# DAC.net
KiCad netlist of a schematic drawn in Altium Designer
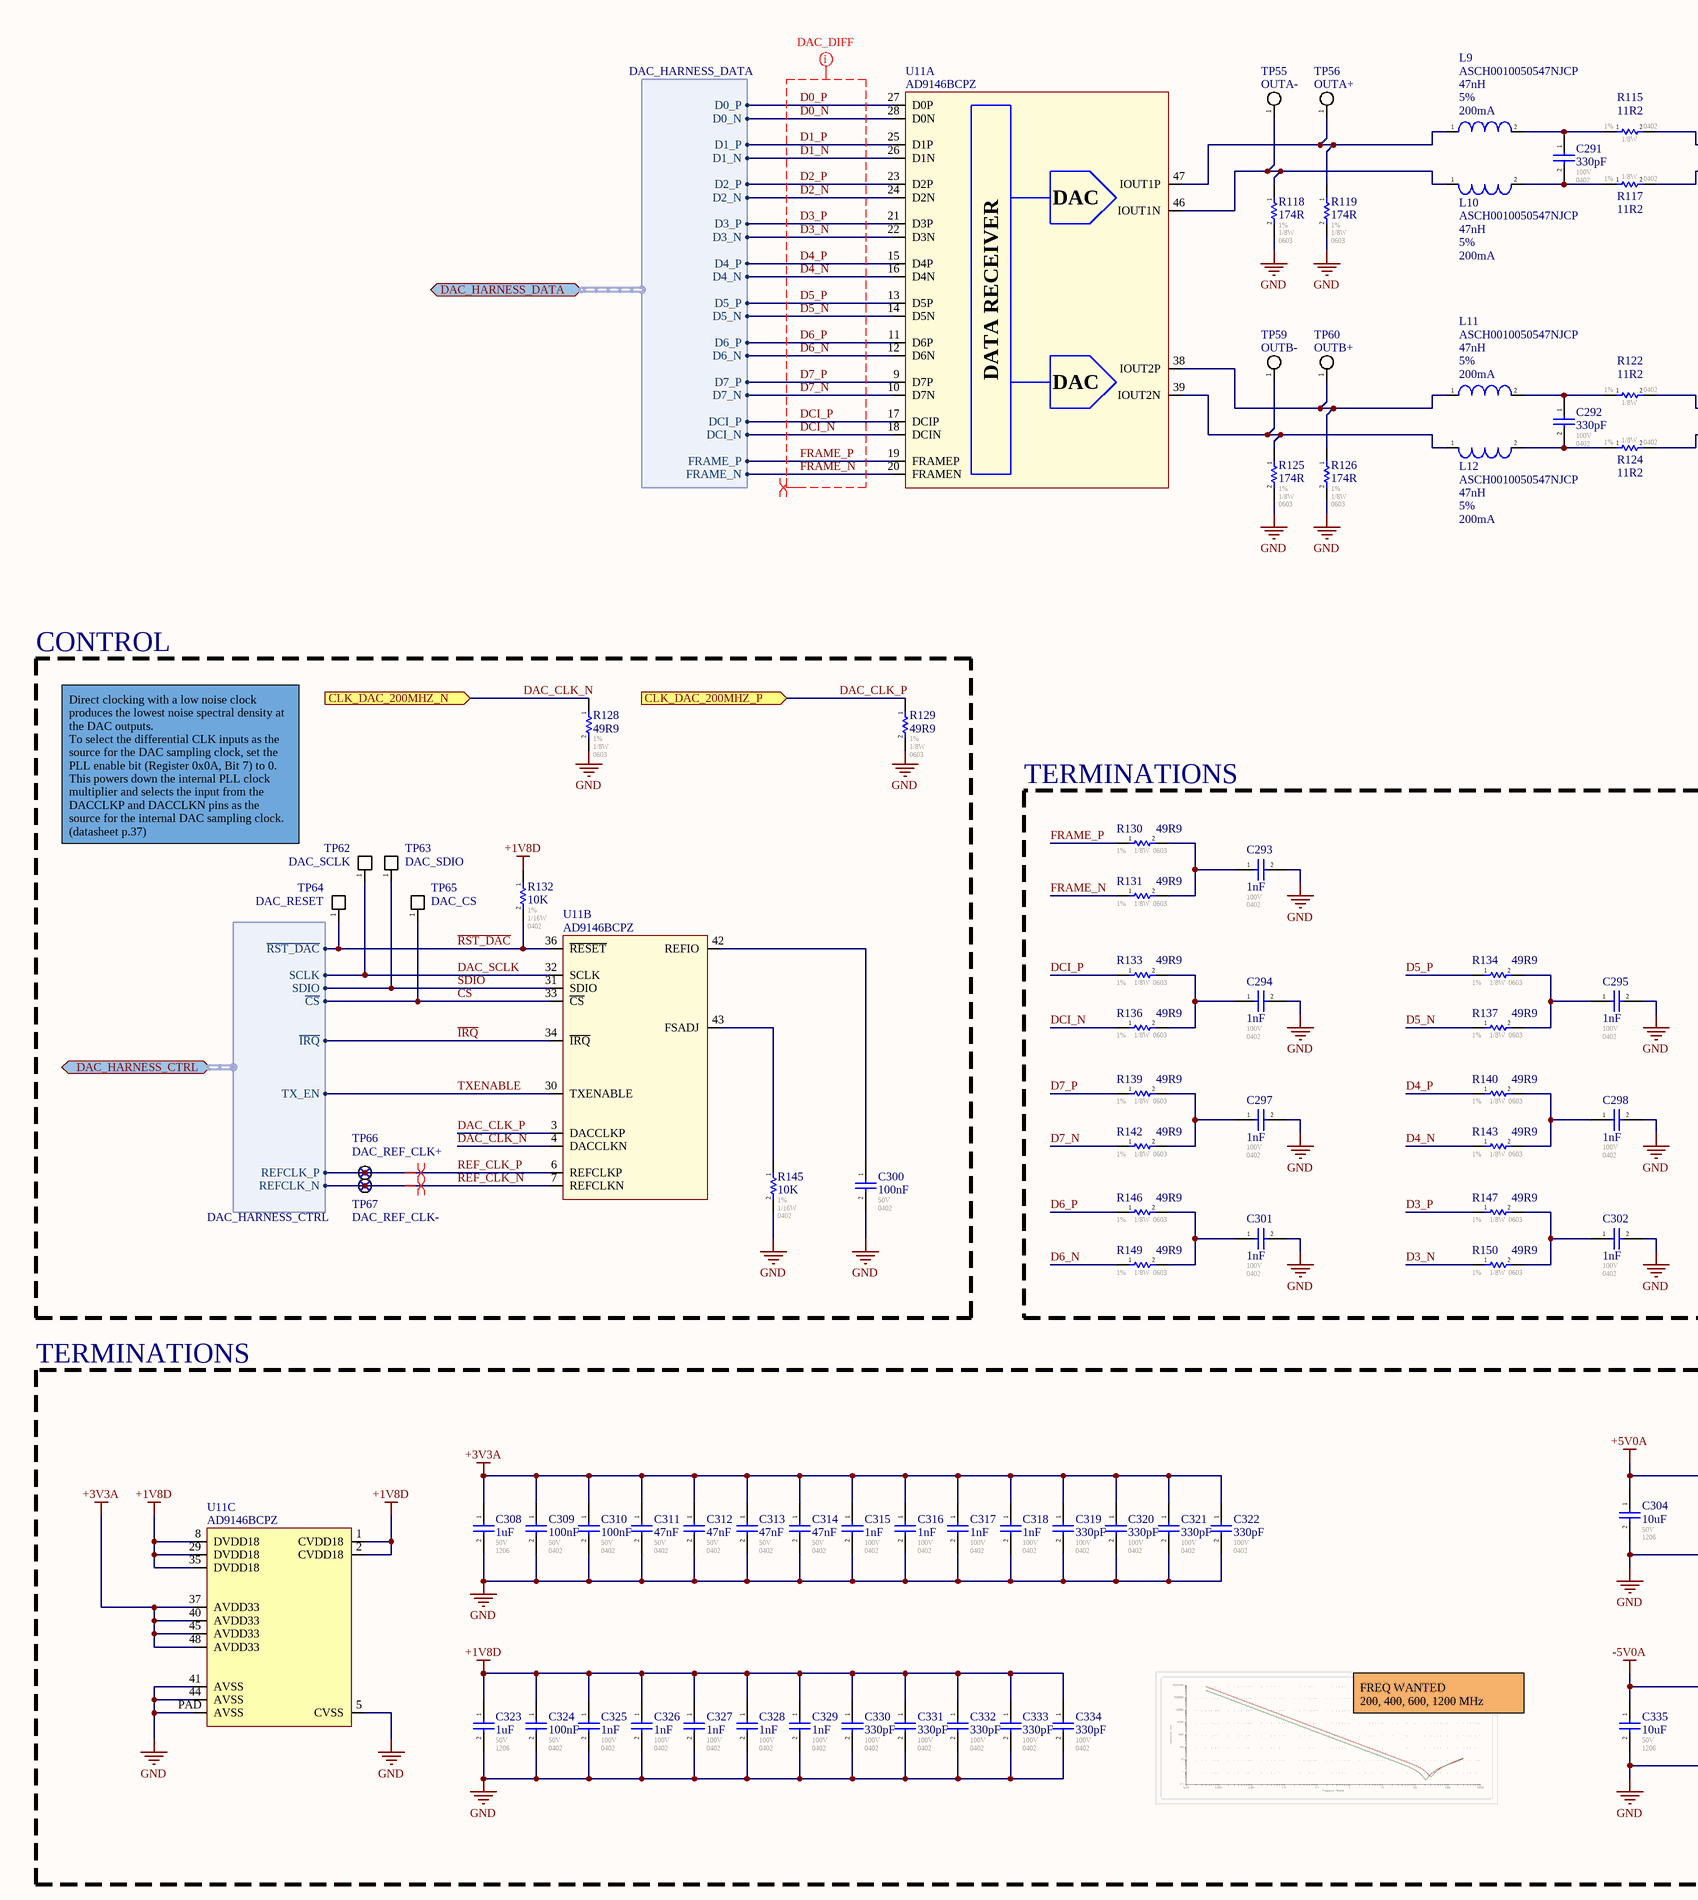
[diagram p0: DAC.SchDoc, left]
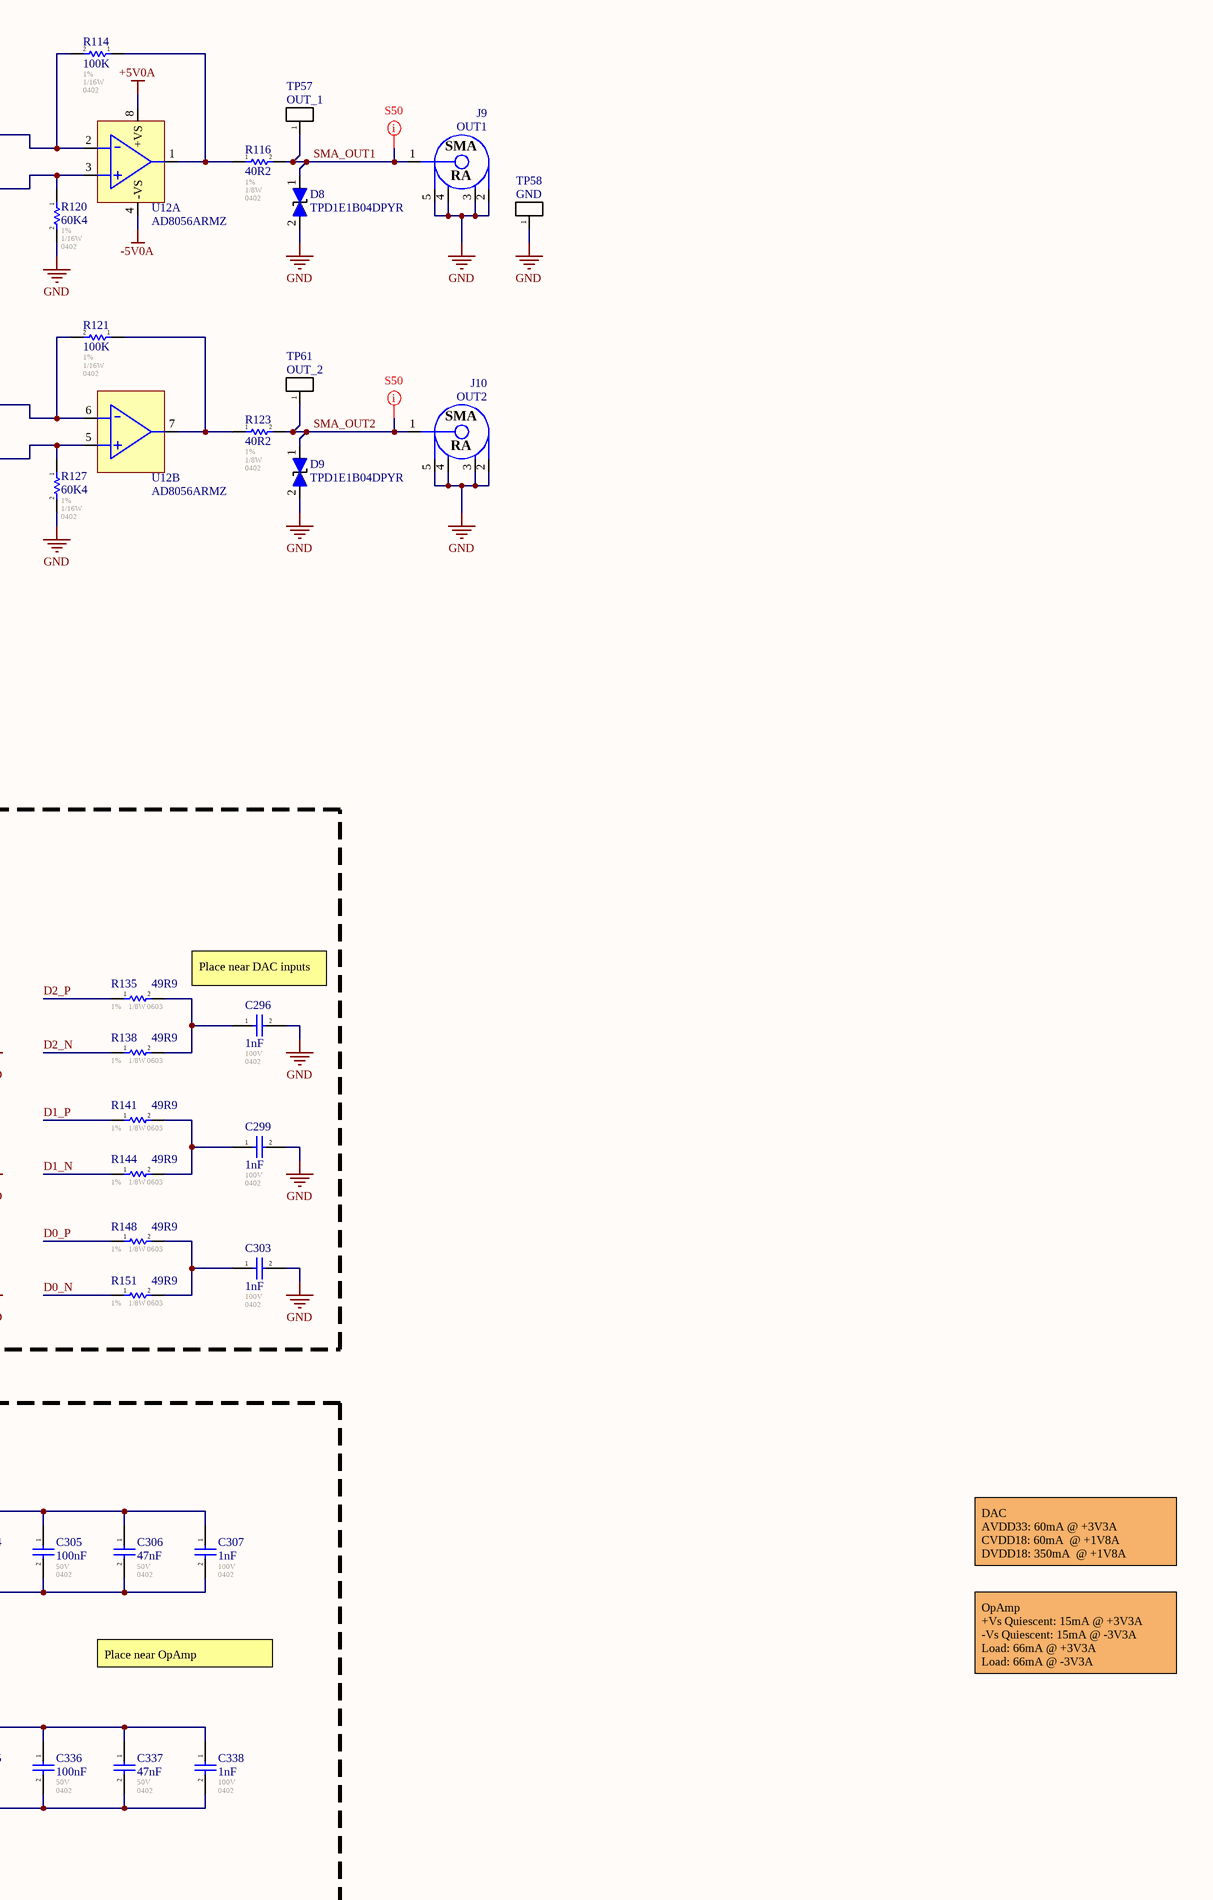
[diagram p1: DAC.SchDoc, right]

(export (version "E")
  (design (tool "Eeschema 10.0.6"))
  (components
    (comp (ref "C291")
      (value "330pF")
      (footprint "0402")
      (description "GCM155R72A331KA37D\r\n0402 330pF 10% X7R Ceramic Capacitor")
      (fields
        (field (name "MFR") "Murata")
        (field (name "PART#") "GCM155R72A331KA37D")
        (field (name "VOLTAGE - RATED") "100V")
      )
      (libsource (lib "Symbols") (part "CAP_CER"))
    )
    (comp (ref "C292")
      (value "330pF")
      (footprint "0402")
      (description "GCM155R72A331KA37D\r\n0402 330pF 10% X7R Ceramic Capacitor")
      (fields
        (field (name "MFR") "Murata")
        (field (name "PART#") "GCM155R72A331KA37D")
        (field (name "VOLTAGE - RATED") "100V")
      )
      (libsource (lib "Symbols") (part "CAP_CER"))
    )
    (comp (ref "C293")
      (value "1nF")
      (footprint "0402")
      (description "GCM155R72A102KA37D\r\n0402 1nF 10% X7R Ceramic Capacitor")
      (fields
        (field (name "MFR") "Murata")
        (field (name "PART#") "GCM155R72A102KA37D")
        (field (name "VOLTAGE - RATED") "100V")
      )
      (libsource (lib "Symbols") (part "CAP_CER"))
    )
    (comp (ref "C294")
      (value "1nF")
      (footprint "0402")
      (description "GCM155R72A102KA37D\r\n0402 1nF 10% X7R Ceramic Capacitor")
      (fields
        (field (name "MFR") "Murata")
        (field (name "PART#") "GCM155R72A102KA37D")
        (field (name "VOLTAGE - RATED") "100V")
      )
      (libsource (lib "Symbols") (part "CAP_CER"))
    )
    (comp (ref "C295")
      (value "1nF")
      (footprint "0402")
      (description "GCM155R72A102KA37D\r\n0402 1nF 10% X7R Ceramic Capacitor")
      (fields
        (field (name "MFR") "Murata")
        (field (name "PART#") "GCM155R72A102KA37D")
        (field (name "VOLTAGE - RATED") "100V")
      )
      (libsource (lib "Symbols") (part "CAP_CER"))
    )
    (comp (ref "C296")
      (value "1nF")
      (footprint "0402")
      (description "GCM155R72A102KA37D\r\n0402 1nF 10% X7R Ceramic Capacitor")
      (fields
        (field (name "MFR") "Murata")
        (field (name "PART#") "GCM155R72A102KA37D")
        (field (name "VOLTAGE - RATED") "100V")
      )
      (libsource (lib "Symbols") (part "CAP_CER"))
    )
    (comp (ref "C297")
      (value "1nF")
      (footprint "0402")
      (description "GCM155R72A102KA37D\r\n0402 1nF 10% X7R Ceramic Capacitor")
      (fields
        (field (name "MFR") "Murata")
        (field (name "PART#") "GCM155R72A102KA37D")
        (field (name "VOLTAGE - RATED") "100V")
      )
      (libsource (lib "Symbols") (part "CAP_CER"))
    )
    (comp (ref "C298")
      (value "1nF")
      (footprint "0402")
      (description "GCM155R72A102KA37D\r\n0402 1nF 10% X7R Ceramic Capacitor")
      (fields
        (field (name "MFR") "Murata")
        (field (name "PART#") "GCM155R72A102KA37D")
        (field (name "VOLTAGE - RATED") "100V")
      )
      (libsource (lib "Symbols") (part "CAP_CER"))
    )
    (comp (ref "C299")
      (value "1nF")
      (footprint "0402")
      (description "GCM155R72A102KA37D\r\n0402 1nF 10% X7R Ceramic Capacitor")
      (fields
        (field (name "MFR") "Murata")
        (field (name "PART#") "GCM155R72A102KA37D")
        (field (name "VOLTAGE - RATED") "100V")
      )
      (libsource (lib "Symbols") (part "CAP_CER"))
    )
    (comp (ref "C300")
      (value "100nF")
      (footprint "0402")
      (description "GCM155R71H104KE02J\r\n0402 100nF 10% X7R Ceramic Capacitor")
      (fields
        (field (name "MFR") "Murata")
        (field (name "PART#") "GCM155R71H104KE02J")
        (field (name "VOLTAGE - RATED") "50V")
      )
      (libsource (lib "Symbols") (part "CAP_CER"))
    )
    (comp (ref "C301")
      (value "1nF")
      (footprint "0402")
      (description "GCM155R72A102KA37D\r\n0402 1nF 10% X7R Ceramic Capacitor")
      (fields
        (field (name "MFR") "Murata")
        (field (name "PART#") "GCM155R72A102KA37D")
        (field (name "VOLTAGE - RATED") "100V")
      )
      (libsource (lib "Symbols") (part "CAP_CER"))
    )
    (comp (ref "C302")
      (value "1nF")
      (footprint "0402")
      (description "GCM155R72A102KA37D\r\n0402 1nF 10% X7R Ceramic Capacitor")
      (fields
        (field (name "MFR") "Murata")
        (field (name "PART#") "GCM155R72A102KA37D")
        (field (name "VOLTAGE - RATED") "100V")
      )
      (libsource (lib "Symbols") (part "CAP_CER"))
    )
    (comp (ref "C303")
      (value "1nF")
      (footprint "0402")
      (description "GCM155R72A102KA37D\r\n0402 1nF 10% X7R Ceramic Capacitor")
      (fields
        (field (name "MFR") "Murata")
        (field (name "PART#") "GCM155R72A102KA37D")
        (field (name "VOLTAGE - RATED") "100V")
      )
      (libsource (lib "Symbols") (part "CAP_CER"))
    )
    (comp (ref "C304")
      (value "10uF")
      (footprint "1206")
      (description "GRT31CR61H106KE01L\r\n1206 10uF 10% X5R Ceramic Capacitor")
      (fields
        (field (name "MFR") "Murata")
        (field (name "VOLTAGE - RATED") "50V")
        (field (name "TOLERANCE") "10%")
      )
      (libsource (lib "Symbols") (part "CAP_CER"))
    )
    (comp (ref "C305")
      (value "100nF")
      (footprint "0402")
      (description "GCM155R71H104KE02J\r\n0402 100nF 10% X7R Ceramic Capacitor")
      (fields
        (field (name "MFR") "Murata")
        (field (name "PART#") "GCM155R71H104KE02J")
        (field (name "VOLTAGE - RATED") "50V")
      )
      (libsource (lib "Symbols") (part "CAP_CER"))
    )
    (comp (ref "C306")
      (value "47nF")
      (footprint "0402")
      (description "GCM155R71H473KE02J\r\n0402 47nF 10% X7R Ceramic Capacitor")
      (fields
        (field (name "MFR") "Murata")
        (field (name "PART#") "GCM155R71H473KE02J")
        (field (name "VOLTAGE - RATED") "50V")
      )
      (libsource (lib "Symbols") (part "CAP_CER"))
    )
    (comp (ref "C307")
      (value "1nF")
      (footprint "0402")
      (description "GCM155R72A102KA37D\r\n0402 1nF 10% X7R Ceramic Capacitor")
      (fields
        (field (name "MFR") "Murata")
        (field (name "PART#") "GCM155R72A102KA37D")
        (field (name "VOLTAGE - RATED") "100V")
      )
      (libsource (lib "Symbols") (part "CAP_CER"))
    )
    (comp (ref "C308")
      (value "1uF")
      (footprint "1206")
      (description "GCJ31CR71H105KA12L\r\n1206 1uF 10% X7R Ceramic Capacitor")
      (fields
        (field (name "MFR") "Murata")
        (field (name "PART#") "GCJ31CR71H105KA12L")
        (field (name "VOLTAGE - RATED") "50V")
      )
      (libsource (lib "Symbols") (part "CAP_CER"))
    )
    (comp (ref "C309")
      (value "100nF")
      (footprint "0402")
      (description "GCM155R71H104KE02J\r\n0402 100nF 10% X7R Ceramic Capacitor")
      (fields
        (field (name "MFR") "Murata")
        (field (name "PART#") "GCM155R71H104KE02J")
        (field (name "VOLTAGE - RATED") "50V")
      )
      (libsource (lib "Symbols") (part "CAP_CER"))
    )
    (comp (ref "C310")
      (value "100nF")
      (footprint "0402")
      (description "GCM155R71H104KE02J\r\n0402 100nF 10% X7R Ceramic Capacitor")
      (fields
        (field (name "MFR") "Murata")
        (field (name "PART#") "GCM155R71H104KE02J")
        (field (name "VOLTAGE - RATED") "50V")
      )
      (libsource (lib "Symbols") (part "CAP_CER"))
    )
    (comp (ref "C311")
      (value "47nF")
      (footprint "0402")
      (description "GCM155R71H473KE02J\r\n0402 47nF 10% X7R Ceramic Capacitor")
      (fields
        (field (name "MFR") "Murata")
        (field (name "PART#") "GCM155R71H473KE02J")
        (field (name "VOLTAGE - RATED") "50V")
      )
      (libsource (lib "Symbols") (part "CAP_CER"))
    )
    (comp (ref "C312")
      (value "47nF")
      (footprint "0402")
      (description "GCM155R71H473KE02J\r\n0402 47nF 10% X7R Ceramic Capacitor")
      (fields
        (field (name "MFR") "Murata")
        (field (name "PART#") "GCM155R71H473KE02J")
        (field (name "VOLTAGE - RATED") "50V")
      )
      (libsource (lib "Symbols") (part "CAP_CER"))
    )
    (comp (ref "C313")
      (value "47nF")
      (footprint "0402")
      (description "GCM155R71H473KE02J\r\n0402 47nF 10% X7R Ceramic Capacitor")
      (fields
        (field (name "MFR") "Murata")
        (field (name "PART#") "GCM155R71H473KE02J")
        (field (name "VOLTAGE - RATED") "50V")
      )
      (libsource (lib "Symbols") (part "CAP_CER"))
    )
    (comp (ref "C314")
      (value "47nF")
      (footprint "0402")
      (description "GCM155R71H473KE02J\r\n0402 47nF 10% X7R Ceramic Capacitor")
      (fields
        (field (name "MFR") "Murata")
        (field (name "PART#") "GCM155R71H473KE02J")
        (field (name "VOLTAGE - RATED") "50V")
      )
      (libsource (lib "Symbols") (part "CAP_CER"))
    )
    (comp (ref "C315")
      (value "1nF")
      (footprint "0402")
      (description "GCM155R72A102KA37D\r\n0402 1nF 10% X7R Ceramic Capacitor")
      (fields
        (field (name "MFR") "Murata")
        (field (name "PART#") "GCM155R72A102KA37D")
        (field (name "VOLTAGE - RATED") "100V")
      )
      (libsource (lib "Symbols") (part "CAP_CER"))
    )
    (comp (ref "C316")
      (value "1nF")
      (footprint "0402")
      (description "GCM155R72A102KA37D\r\n0402 1nF 10% X7R Ceramic Capacitor")
      (fields
        (field (name "MFR") "Murata")
        (field (name "PART#") "GCM155R72A102KA37D")
        (field (name "VOLTAGE - RATED") "100V")
      )
      (libsource (lib "Symbols") (part "CAP_CER"))
    )
    (comp (ref "C317")
      (value "1nF")
      (footprint "0402")
      (description "GCM155R72A102KA37D\r\n0402 1nF 10% X7R Ceramic Capacitor")
      (fields
        (field (name "MFR") "Murata")
        (field (name "PART#") "GCM155R72A102KA37D")
        (field (name "VOLTAGE - RATED") "100V")
      )
      (libsource (lib "Symbols") (part "CAP_CER"))
    )
    (comp (ref "C318")
      (value "1nF")
      (footprint "0402")
      (description "GCM155R72A102KA37D\r\n0402 1nF 10% X7R Ceramic Capacitor")
      (fields
        (field (name "MFR") "Murata")
        (field (name "PART#") "GCM155R72A102KA37D")
        (field (name "VOLTAGE - RATED") "100V")
      )
      (libsource (lib "Symbols") (part "CAP_CER"))
    )
    (comp (ref "C319")
      (value "330pF")
      (footprint "0402")
      (description "GCM155R72A331KA37D\r\n0402 330pF 10% X7R Ceramic Capacitor")
      (fields
        (field (name "MFR") "Murata")
        (field (name "PART#") "GCM155R72A331KA37D")
        (field (name "VOLTAGE - RATED") "100V")
      )
      (libsource (lib "Symbols") (part "CAP_CER"))
    )
    (comp (ref "C320")
      (value "330pF")
      (footprint "0402")
      (description "GCM155R72A331KA37D\r\n0402 330pF 10% X7R Ceramic Capacitor")
      (fields
        (field (name "MFR") "Murata")
        (field (name "PART#") "GCM155R72A331KA37D")
        (field (name "VOLTAGE - RATED") "100V")
      )
      (libsource (lib "Symbols") (part "CAP_CER"))
    )
    (comp (ref "C321")
      (value "330pF")
      (footprint "0402")
      (description "GCM155R72A331KA37D\r\n0402 330pF 10% X7R Ceramic Capacitor")
      (fields
        (field (name "MFR") "Murata")
        (field (name "PART#") "GCM155R72A331KA37D")
        (field (name "VOLTAGE - RATED") "100V")
      )
      (libsource (lib "Symbols") (part "CAP_CER"))
    )
    (comp (ref "C322")
      (value "330pF")
      (footprint "0402")
      (description "GCM155R72A331KA37D\r\n0402 330pF 10% X7R Ceramic Capacitor")
      (fields
        (field (name "MFR") "Murata")
        (field (name "PART#") "GCM155R72A331KA37D")
        (field (name "VOLTAGE - RATED") "100V")
      )
      (libsource (lib "Symbols") (part "CAP_CER"))
    )
    (comp (ref "C323")
      (value "1uF")
      (footprint "1206")
      (description "GCJ31CR71H105KA12L\r\n1206 1uF 10% X7R Ceramic Capacitor")
      (fields
        (field (name "MFR") "Murata")
        (field (name "PART#") "GCJ31CR71H105KA12L")
        (field (name "VOLTAGE - RATED") "50V")
      )
      (libsource (lib "Symbols") (part "CAP_CER"))
    )
    (comp (ref "C324")
      (value "100nF")
      (footprint "0402")
      (description "GCM155R71H104KE02J\r\n0402 100nF 10% X7R Ceramic Capacitor")
      (fields
        (field (name "MFR") "Murata")
        (field (name "PART#") "GCM155R71H104KE02J")
        (field (name "VOLTAGE - RATED") "50V")
      )
      (libsource (lib "Symbols") (part "CAP_CER"))
    )
    (comp (ref "C325")
      (value "1nF")
      (footprint "0402")
      (description "GCM155R72A102KA37D\r\n0402 1nF 10% X7R Ceramic Capacitor")
      (fields
        (field (name "MFR") "Murata")
        (field (name "PART#") "GCM155R72A102KA37D")
        (field (name "VOLTAGE - RATED") "100V")
      )
      (libsource (lib "Symbols") (part "CAP_CER"))
    )
    (comp (ref "C326")
      (value "1nF")
      (footprint "0402")
      (description "GCM155R72A102KA37D\r\n0402 1nF 10% X7R Ceramic Capacitor")
      (fields
        (field (name "MFR") "Murata")
        (field (name "PART#") "GCM155R72A102KA37D")
        (field (name "VOLTAGE - RATED") "100V")
      )
      (libsource (lib "Symbols") (part "CAP_CER"))
    )
    (comp (ref "C327")
      (value "1nF")
      (footprint "0402")
      (description "GCM155R72A102KA37D\r\n0402 1nF 10% X7R Ceramic Capacitor")
      (fields
        (field (name "MFR") "Murata")
        (field (name "PART#") "GCM155R72A102KA37D")
        (field (name "VOLTAGE - RATED") "100V")
      )
      (libsource (lib "Symbols") (part "CAP_CER"))
    )
    (comp (ref "C328")
      (value "1nF")
      (footprint "0402")
      (description "GCM155R72A102KA37D\r\n0402 1nF 10% X7R Ceramic Capacitor")
      (fields
        (field (name "MFR") "Murata")
        (field (name "PART#") "GCM155R72A102KA37D")
        (field (name "VOLTAGE - RATED") "100V")
      )
      (libsource (lib "Symbols") (part "CAP_CER"))
    )
    (comp (ref "C329")
      (value "1nF")
      (footprint "0402")
      (description "GCM155R72A102KA37D\r\n0402 1nF 10% X7R Ceramic Capacitor")
      (fields
        (field (name "MFR") "Murata")
        (field (name "PART#") "GCM155R72A102KA37D")
        (field (name "VOLTAGE - RATED") "100V")
      )
      (libsource (lib "Symbols") (part "CAP_CER"))
    )
    (comp (ref "C330")
      (value "330pF")
      (footprint "0402")
      (description "GCM155R72A331KA37D\r\n0402 330pF 10% X7R Ceramic Capacitor")
      (fields
        (field (name "MFR") "Murata")
        (field (name "PART#") "GCM155R72A331KA37D")
        (field (name "VOLTAGE - RATED") "100V")
      )
      (libsource (lib "Symbols") (part "CAP_CER"))
    )
    (comp (ref "C331")
      (value "330pF")
      (footprint "0402")
      (description "GCM155R72A331KA37D\r\n0402 330pF 10% X7R Ceramic Capacitor")
      (fields
        (field (name "MFR") "Murata")
        (field (name "PART#") "GCM155R72A331KA37D")
        (field (name "VOLTAGE - RATED") "100V")
      )
      (libsource (lib "Symbols") (part "CAP_CER"))
    )
    (comp (ref "C332")
      (value "330pF")
      (footprint "0402")
      (description "GCM155R72A331KA37D\r\n0402 330pF 10% X7R Ceramic Capacitor")
      (fields
        (field (name "MFR") "Murata")
        (field (name "PART#") "GCM155R72A331KA37D")
        (field (name "VOLTAGE - RATED") "100V")
      )
      (libsource (lib "Symbols") (part "CAP_CER"))
    )
    (comp (ref "C333")
      (value "330pF")
      (footprint "0402")
      (description "GCM155R72A331KA37D\r\n0402 330pF 10% X7R Ceramic Capacitor")
      (fields
        (field (name "MFR") "Murata")
        (field (name "PART#") "GCM155R72A331KA37D")
        (field (name "VOLTAGE - RATED") "100V")
      )
      (libsource (lib "Symbols") (part "CAP_CER"))
    )
    (comp (ref "C334")
      (value "330pF")
      (footprint "0402")
      (description "GCM155R72A331KA37D\r\n0402 330pF 10% X7R Ceramic Capacitor")
      (fields
        (field (name "MFR") "Murata")
        (field (name "PART#") "GCM155R72A331KA37D")
        (field (name "VOLTAGE - RATED") "100V")
      )
      (libsource (lib "Symbols") (part "CAP_CER"))
    )
    (comp (ref "C335")
      (value "10uF")
      (footprint "1206")
      (description "GRT31CR61H106KE01L\r\n1206 10uF 10% X5R Ceramic Capacitor")
      (fields
        (field (name "MFR") "Murata")
        (field (name "VOLTAGE - RATED") "50V")
        (field (name "TOLERANCE") "10%")
      )
      (libsource (lib "Symbols") (part "CAP_CER"))
    )
    (comp (ref "C336")
      (value "100nF")
      (footprint "0402")
      (description "GCM155R71H104KE02J\r\n0402 100nF 10% X7R Ceramic Capacitor")
      (fields
        (field (name "MFR") "Murata")
        (field (name "PART#") "GCM155R71H104KE02J")
        (field (name "VOLTAGE - RATED") "50V")
      )
      (libsource (lib "Symbols") (part "CAP_CER"))
    )
    (comp (ref "C337")
      (value "47nF")
      (footprint "0402")
      (description "GCM155R71H473KE02J\r\n0402 47nF 10% X7R Ceramic Capacitor")
      (fields
        (field (name "MFR") "Murata")
        (field (name "PART#") "GCM155R71H473KE02J")
        (field (name "VOLTAGE - RATED") "50V")
      )
      (libsource (lib "Symbols") (part "CAP_CER"))
    )
    (comp (ref "C338")
      (value "1nF")
      (footprint "0402")
      (description "GCM155R72A102KA37D\r\n0402 1nF 10% X7R Ceramic Capacitor")
      (fields
        (field (name "MFR") "Murata")
        (field (name "PART#") "GCM155R72A102KA37D")
        (field (name "VOLTAGE - RATED") "100V")
      )
      (libsource (lib "Symbols") (part "CAP_CER"))
    )
    (comp (ref "D8")
      (value "TPD1E1B04DPYR")
      (footprint "TVS_DATA_TPD1E1B04DPYR")
      (description "TVS - TVS DIODE 3.6V 8.5V - 0402")
      (fields
        (field (name "CREATEDBY/DATE") "Keven Deslandes - 2018/10/19")
        (field (name "VERIFIEDBY") "Caroline Paulin - 28 janv 2019")
      )
      (libsource (lib "S7CAS_LIB2023") (part "TVS_DATA_TPD1E1B04DPYR"))
    )
    (comp (ref "D9")
      (value "TPD1E1B04DPYR")
      (footprint "TVS_DATA_TPD1E1B04DPYR")
      (description "TVS - TVS DIODE 3.6V 8.5V - 0402")
      (fields
        (field (name "CREATEDBY/DATE") "Keven Deslandes - 2018/10/19")
        (field (name "VERIFIEDBY") "Caroline Paulin - 28 janv 2019")
      )
      (libsource (lib "S7CAS_LIB2023") (part "TVS_DATA_TPD1E1B04DPYR"))
    )
    (comp (ref "J9")
      (value "OUT1")
      (footprint "CONN_SMA_5-1814400-1")
      (description "5-1814400-1\r\nCONN -  SMA JACK R/A 50 OHM - TH")
      (fields
        (field (name "MFG") "TE Connectivity AMP Connectors")
        (field (name "MFG PART NUMBER") "5-1814400-1")
        (field (name "CREATEDBY") "Jonathan Bouchard")
      )
      (libsource (lib "S7CAS_LIB2023") (part "CONN_SMA_5-1814400-1"))
    )
    (comp (ref "J10")
      (value "OUT2")
      (footprint "CONN_SMA_5-1814400-1")
      (description "5-1814400-1\r\nCONN -  SMA JACK R/A 50 OHM - TH")
      (fields
        (field (name "MFG") "TE Connectivity AMP Connectors")
        (field (name "MFG PART NUMBER") "5-1814400-1")
        (field (name "CREATEDBY") "Jonathan Bouchard")
      )
      (libsource (lib "S7CAS_LIB2023") (part "CONN_SMA_5-1814400-1"))
    )
    (comp (ref "L9")
      (value "ASCH0010050547NJCP")
      (footprint "IND_0402")
      (description "Generic Inductor")
      (fields
        (field (name "INDUCTANCE") "47nH")
        (field (name "TOLERANCE") "5%")
        (field (name "CURRENT RATING") "200mA")
      )
      (libsource (lib "Symbols") (part "INDUCTOR"))
    )
    (comp (ref "L10")
      (value "ASCH0010050547NJCP")
      (footprint "IND_0402")
      (description "Generic Inductor")
      (fields
        (field (name "INDUCTANCE") "47nH")
        (field (name "TOLERANCE") "5%")
        (field (name "CURRENT RATING") "200mA")
      )
      (libsource (lib "Symbols") (part "INDUCTOR"))
    )
    (comp (ref "L11")
      (value "ASCH0010050547NJCP")
      (footprint "IND_0402")
      (description "Generic Inductor")
      (fields
        (field (name "INDUCTANCE") "47nH")
        (field (name "TOLERANCE") "5%")
        (field (name "CURRENT RATING") "200mA")
      )
      (libsource (lib "Symbols") (part "INDUCTOR"))
    )
    (comp (ref "L12")
      (value "ASCH0010050547NJCP")
      (footprint "IND_0402")
      (description "Generic Inductor")
      (fields
        (field (name "INDUCTANCE") "47nH")
        (field (name "TOLERANCE") "5%")
        (field (name "CURRENT RATING") "200mA")
      )
      (libsource (lib "Symbols") (part "INDUCTOR"))
    )
    (comp (ref "R114")
      (value "100K")
      (footprint "RES_0402")
      (fields
        (field (name "TOLERANCE") "1%")
        (field (name "POWER") "1/16W")
        (field (name "PACKAGE / CASE") "0402")
      )
      (libsource (lib "Symbols") (part "RESISTOR"))
    )
    (comp (ref "R115")
      (value "11R2")
      (footprint "RES_0402")
      (fields
        (field (name "TOLERANCE") "1%")
        (field (name "POWER") "1/8W")
        (field (name "PACKAGE / CASE") "0402")
      )
      (libsource (lib "Symbols") (part "RESISTOR"))
    )
    (comp (ref "R116")
      (value "40R2")
      (footprint "RES_0402")
      (fields
        (field (name "TOLERANCE") "1%")
        (field (name "POWER") "1/8W")
        (field (name "PACKAGE / CASE") "0402")
      )
      (libsource (lib "Symbols") (part "RESISTOR"))
    )
    (comp (ref "R117")
      (value "11R2")
      (footprint "RES_0402")
      (fields
        (field (name "TOLERANCE") "1%")
        (field (name "POWER") "1/8W")
        (field (name "PACKAGE / CASE") "0402")
      )
      (libsource (lib "Symbols") (part "RESISTOR"))
    )
    (comp (ref "R118")
      (value "174R")
      (footprint "RES_0603")
      (fields
        (field (name "TOLERANCE") "1%")
        (field (name "POWER") "1/8W")
        (field (name "PACKAGE / CASE") "0603")
      )
      (libsource (lib "Symbols") (part "RESISTOR"))
    )
    (comp (ref "R119")
      (value "174R")
      (footprint "RES_0603")
      (fields
        (field (name "TOLERANCE") "1%")
        (field (name "POWER") "1/8W")
        (field (name "PACKAGE / CASE") "0603")
      )
      (libsource (lib "Symbols") (part "RESISTOR"))
    )
    (comp (ref "R120")
      (value "60K4")
      (footprint "RES_0402")
      (description "RMCF0402FT60K4")
      (fields
        (field (name "TOLERANCE") "1%")
        (field (name "POWER") "1/16W")
        (field (name "PACKAGE / CASE") "0402")
      )
      (libsource (lib "Symbols") (part "RESISTOR"))
    )
    (comp (ref "R121")
      (value "100K")
      (footprint "RES_0402")
      (fields
        (field (name "TOLERANCE") "1%")
        (field (name "POWER") "1/16W")
        (field (name "PACKAGE / CASE") "0402")
      )
      (libsource (lib "Symbols") (part "RESISTOR"))
    )
    (comp (ref "R122")
      (value "11R2")
      (footprint "RES_0402")
      (fields
        (field (name "TOLERANCE") "1%")
        (field (name "POWER") "1/8W")
        (field (name "PACKAGE / CASE") "0402")
      )
      (libsource (lib "Symbols") (part "RESISTOR"))
    )
    (comp (ref "R123")
      (value "40R2")
      (footprint "RES_0402")
      (fields
        (field (name "TOLERANCE") "1%")
        (field (name "POWER") "1/8W")
        (field (name "PACKAGE / CASE") "0402")
      )
      (libsource (lib "Symbols") (part "RESISTOR"))
    )
    (comp (ref "R124")
      (value "11R2")
      (footprint "RES_0402")
      (fields
        (field (name "TOLERANCE") "1%")
        (field (name "POWER") "1/8W")
        (field (name "PACKAGE / CASE") "0402")
      )
      (libsource (lib "Symbols") (part "RESISTOR"))
    )
    (comp (ref "R125")
      (value "174R")
      (footprint "RES_0603")
      (fields
        (field (name "TOLERANCE") "1%")
        (field (name "POWER") "1/8W")
        (field (name "PACKAGE / CASE") "0603")
      )
      (libsource (lib "Symbols") (part "RESISTOR"))
    )
    (comp (ref "R126")
      (value "174R")
      (footprint "RES_0603")
      (fields
        (field (name "TOLERANCE") "1%")
        (field (name "POWER") "1/8W")
        (field (name "PACKAGE / CASE") "0603")
      )
      (libsource (lib "Symbols") (part "RESISTOR"))
    )
    (comp (ref "R127")
      (value "60K4")
      (footprint "RES_0402")
      (description "RMCF0402FT60K4")
      (fields
        (field (name "TOLERANCE") "1%")
        (field (name "POWER") "1/16W")
        (field (name "PACKAGE / CASE") "0402")
      )
      (libsource (lib "Symbols") (part "RESISTOR"))
    )
    (comp (ref "R128")
      (value "49R9")
      (footprint "RES_0603")
      (fields
        (field (name "TOLERANCE") "1%")
        (field (name "POWER") "1/8W")
        (field (name "PACKAGE / CASE") "0603")
      )
      (libsource (lib "Symbols") (part "RESISTOR"))
    )
    (comp (ref "R129")
      (value "49R9")
      (footprint "RES_0603")
      (fields
        (field (name "TOLERANCE") "1%")
        (field (name "POWER") "1/8W")
        (field (name "PACKAGE / CASE") "0603")
      )
      (libsource (lib "Symbols") (part "RESISTOR"))
    )
    (comp (ref "R130")
      (value "49R9")
      (footprint "RES_0603")
      (fields
        (field (name "TOLERANCE") "1%")
        (field (name "POWER") "1/8W")
        (field (name "PACKAGE / CASE") "0603")
      )
      (libsource (lib "Symbols") (part "RESISTOR"))
    )
    (comp (ref "R131")
      (value "49R9")
      (footprint "RES_0603")
      (fields
        (field (name "TOLERANCE") "1%")
        (field (name "POWER") "1/8W")
        (field (name "PACKAGE / CASE") "0603")
      )
      (libsource (lib "Symbols") (part "RESISTOR"))
    )
    (comp (ref "R132")
      (value "10K")
      (footprint "RES_0402")
      (fields
        (field (name "TOLERANCE") "1%")
        (field (name "POWER") "1/16W")
        (field (name "PACKAGE / CASE") "0402")
      )
      (libsource (lib "Symbols") (part "RESISTOR"))
    )
    (comp (ref "R133")
      (value "49R9")
      (footprint "RES_0603")
      (fields
        (field (name "TOLERANCE") "1%")
        (field (name "POWER") "1/8W")
        (field (name "PACKAGE / CASE") "0603")
      )
      (libsource (lib "Symbols") (part "RESISTOR"))
    )
    (comp (ref "R134")
      (value "49R9")
      (footprint "RES_0603")
      (fields
        (field (name "TOLERANCE") "1%")
        (field (name "POWER") "1/8W")
        (field (name "PACKAGE / CASE") "0603")
      )
      (libsource (lib "Symbols") (part "RESISTOR"))
    )
    (comp (ref "R135")
      (value "49R9")
      (footprint "RES_0603")
      (fields
        (field (name "TOLERANCE") "1%")
        (field (name "POWER") "1/8W")
        (field (name "PACKAGE / CASE") "0603")
      )
      (libsource (lib "Symbols") (part "RESISTOR"))
    )
    (comp (ref "R136")
      (value "49R9")
      (footprint "RES_0603")
      (fields
        (field (name "TOLERANCE") "1%")
        (field (name "POWER") "1/8W")
        (field (name "PACKAGE / CASE") "0603")
      )
      (libsource (lib "Symbols") (part "RESISTOR"))
    )
    (comp (ref "R137")
      (value "49R9")
      (footprint "RES_0603")
      (fields
        (field (name "TOLERANCE") "1%")
        (field (name "POWER") "1/8W")
        (field (name "PACKAGE / CASE") "0603")
      )
      (libsource (lib "Symbols") (part "RESISTOR"))
    )
    (comp (ref "R138")
      (value "49R9")
      (footprint "RES_0603")
      (fields
        (field (name "TOLERANCE") "1%")
        (field (name "POWER") "1/8W")
        (field (name "PACKAGE / CASE") "0603")
      )
      (libsource (lib "Symbols") (part "RESISTOR"))
    )
    (comp (ref "R139")
      (value "49R9")
      (footprint "RES_0603")
      (fields
        (field (name "TOLERANCE") "1%")
        (field (name "POWER") "1/8W")
        (field (name "PACKAGE / CASE") "0603")
      )
      (libsource (lib "Symbols") (part "RESISTOR"))
    )
    (comp (ref "R140")
      (value "49R9")
      (footprint "RES_0603")
      (fields
        (field (name "TOLERANCE") "1%")
        (field (name "POWER") "1/8W")
        (field (name "PACKAGE / CASE") "0603")
      )
      (libsource (lib "Symbols") (part "RESISTOR"))
    )
    (comp (ref "R141")
      (value "49R9")
      (footprint "RES_0603")
      (fields
        (field (name "TOLERANCE") "1%")
        (field (name "POWER") "1/8W")
        (field (name "PACKAGE / CASE") "0603")
      )
      (libsource (lib "Symbols") (part "RESISTOR"))
    )
    (comp (ref "R142")
      (value "49R9")
      (footprint "RES_0603")
      (fields
        (field (name "TOLERANCE") "1%")
        (field (name "POWER") "1/8W")
        (field (name "PACKAGE / CASE") "0603")
      )
      (libsource (lib "Symbols") (part "RESISTOR"))
    )
    (comp (ref "R143")
      (value "49R9")
      (footprint "RES_0603")
      (fields
        (field (name "TOLERANCE") "1%")
        (field (name "POWER") "1/8W")
        (field (name "PACKAGE / CASE") "0603")
      )
      (libsource (lib "Symbols") (part "RESISTOR"))
    )
    (comp (ref "R144")
      (value "49R9")
      (footprint "RES_0603")
      (fields
        (field (name "TOLERANCE") "1%")
        (field (name "POWER") "1/8W")
        (field (name "PACKAGE / CASE") "0603")
      )
      (libsource (lib "Symbols") (part "RESISTOR"))
    )
    (comp (ref "R145")
      (value "10K")
      (footprint "RES_0402")
      (fields
        (field (name "TOLERANCE") "1%")
        (field (name "POWER") "1/16W")
        (field (name "PACKAGE / CASE") "0402")
      )
      (libsource (lib "Symbols") (part "RESISTOR"))
    )
    (comp (ref "R146")
      (value "49R9")
      (footprint "RES_0603")
      (fields
        (field (name "TOLERANCE") "1%")
        (field (name "POWER") "1/8W")
        (field (name "PACKAGE / CASE") "0603")
      )
      (libsource (lib "Symbols") (part "RESISTOR"))
    )
    (comp (ref "R147")
      (value "49R9")
      (footprint "RES_0603")
      (fields
        (field (name "TOLERANCE") "1%")
        (field (name "POWER") "1/8W")
        (field (name "PACKAGE / CASE") "0603")
      )
      (libsource (lib "Symbols") (part "RESISTOR"))
    )
    (comp (ref "R148")
      (value "49R9")
      (footprint "RES_0603")
      (fields
        (field (name "TOLERANCE") "1%")
        (field (name "POWER") "1/8W")
        (field (name "PACKAGE / CASE") "0603")
      )
      (libsource (lib "Symbols") (part "RESISTOR"))
    )
    (comp (ref "R149")
      (value "49R9")
      (footprint "RES_0603")
      (fields
        (field (name "TOLERANCE") "1%")
        (field (name "POWER") "1/8W")
        (field (name "PACKAGE / CASE") "0603")
      )
      (libsource (lib "Symbols") (part "RESISTOR"))
    )
    (comp (ref "R150")
      (value "49R9")
      (footprint "RES_0603")
      (fields
        (field (name "TOLERANCE") "1%")
        (field (name "POWER") "1/8W")
        (field (name "PACKAGE / CASE") "0603")
      )
      (libsource (lib "Symbols") (part "RESISTOR"))
    )
    (comp (ref "R151")
      (value "49R9")
      (footprint "RES_0603")
      (fields
        (field (name "TOLERANCE") "1%")
        (field (name "POWER") "1/8W")
        (field (name "PACKAGE / CASE") "0603")
      )
      (libsource (lib "Symbols") (part "RESISTOR"))
    )
    (comp (ref "TP55")
      (value "OUTA-")
      (footprint "TP_PAD_SMALL")
      (description "Test Point")
      (libsource (lib "Symbols") (part "TESTPOINT_PAD_SMALL"))
    )
    (comp (ref "TP56")
      (value "OUTA+")
      (footprint "TP_PAD_SMALL")
      (description "Test Point")
      (libsource (lib "Symbols") (part "TESTPOINT_PAD_SMALL"))
    )
    (comp (ref "TP57")
      (value "OUT_1")
      (footprint "TP_HOLE")
      (description "Test Point")
      (libsource (lib "Symbols") (part "TESTPOINT"))
    )
    (comp (ref "TP58")
      (value "GND")
      (footprint "TP_HOLE")
      (description "Test Point")
      (libsource (lib "Symbols") (part "TESTPOINT"))
    )
    (comp (ref "TP59")
      (value "OUTB-")
      (footprint "TP_PAD_SMALL")
      (description "Test Point")
      (libsource (lib "Symbols") (part "TESTPOINT_PAD_SMALL"))
    )
    (comp (ref "TP60")
      (value "OUTB+")
      (footprint "TP_PAD_SMALL")
      (description "Test Point")
      (libsource (lib "Symbols") (part "TESTPOINT_PAD_SMALL"))
    )
    (comp (ref "TP61")
      (value "OUT_2")
      (footprint "TP_HOLE")
      (description "Test Point")
      (libsource (lib "Symbols") (part "TESTPOINT"))
    )
    (comp (ref "TP62")
      (value "DAC_SCLK")
      (footprint "TP_PAD")
      (description "Test Point")
      (libsource (lib "Symbols") (part "TESTPOINT_PAD"))
    )
    (comp (ref "TP63")
      (value "DAC_SDIO")
      (footprint "TP_PAD")
      (description "Test Point")
      (libsource (lib "Symbols") (part "TESTPOINT_PAD"))
    )
    (comp (ref "TP64")
      (value "DAC_RESET")
      (footprint "TP_PAD")
      (description "Test Point")
      (libsource (lib "Symbols") (part "TESTPOINT_PAD"))
    )
    (comp (ref "TP65")
      (value "DAC_CS")
      (footprint "TP_PAD")
      (description "Test Point")
      (libsource (lib "Symbols") (part "TESTPOINT_PAD"))
    )
    (comp (ref "TP66")
      (value "DAC_REF_CLK+")
      (footprint "TP_PAD_TINY")
      (description "Test Point")
      (libsource (lib "Symbols") (part "TESTPOINT_PAD_TINY"))
    )
    (comp (ref "TP67")
      (value "DAC_REF_CLK-")
      (footprint "TP_PAD_TINY")
      (description "Test Point")
      (libsource (lib "Symbols") (part "TESTPOINT_PAD_TINY"))
    )
    (comp (ref "U11")
      (value "AD9146BCPZ")
      (footprint "DAC_AD9146BCPZ")
      (description "DAC - 16BIT SRL HIGH SPEED - QFN-48")
      (fields
        (field (name "VOLTAGE") "3.13 V ~ 3.47 V / 1.71 V ~ 1.89 V")
        (field (name "MFG") "Analog Devices Inc.")
        (field (name "CREATEDBY") "Jonathan Bouchard")
      )
      (libsource (lib "S7CAS_LIB2023") (part "DAC_AD9146BCPZ"))
    )
    (comp (ref "U12")
      (value "AD8056ARMZ")
      (footprint "OPAMP_AD8056ARMZ")
      (description "OPAMP - VFB 300MHZ - 8MSOP")
      (fields
        (field (name "VOLTAGE") "8 V ~ 12 V, ±4 V ~ 6 V")
        (field (name "MFG") "Analog Devices")
        (field (name "CREATEDBY") "Jonathan Bouchard")
      )
      (libsource (lib "S7CAS_LIB2023") (part "OPAMP_AD8056ARMZ"))
    )
  )
  (nets
    (net (code "3") (name "+1V8D") (class "Default")
      (node (ref "C323") (pin "1") (pinfunction "1_1") (pintype "passive"))
      (node (ref "C324") (pin "1") (pinfunction "1_1") (pintype "passive"))
      (node (ref "C325") (pin "1") (pinfunction "1_1") (pintype "passive"))
      (node (ref "C326") (pin "1") (pinfunction "1_1") (pintype "passive"))
      (node (ref "C327") (pin "1") (pinfunction "1_1") (pintype "passive"))
      (node (ref "C328") (pin "1") (pinfunction "1_1") (pintype "passive"))
      (node (ref "C329") (pin "1") (pinfunction "1_1") (pintype "passive"))
      (node (ref "C330") (pin "1") (pinfunction "1_1") (pintype "passive"))
      (node (ref "C331") (pin "1") (pinfunction "1_1") (pintype "passive"))
      (node (ref "C332") (pin "1") (pinfunction "1_1") (pintype "passive"))
      (node (ref "C333") (pin "1") (pinfunction "1_1") (pintype "passive"))
      (node (ref "C334") (pin "1") (pinfunction "1_1") (pintype "passive"))
      (node (ref "R132") (pin "1") (pinfunction "1_1") (pintype "passive"))
      (node (ref "U11") (pin "1") (pinfunction "CVDD18_1") (pintype "passive"))
      (node (ref "U11") (pin "2") (pinfunction "CVDD18_2") (pintype "passive"))
      (node (ref "U11") (pin "29") (pinfunction "DVDD18_29") (pintype "passive"))
      (node (ref "U11") (pin "35") (pinfunction "DVDD18_35") (pintype "passive"))
      (node (ref "U11") (pin "8") (pinfunction "DVDD18_8") (pintype "passive"))
    )
    (net (code "4") (name "+3V3A") (class "Default")
      (node (ref "C308") (pin "1") (pinfunction "1_1") (pintype "passive"))
      (node (ref "C309") (pin "1") (pinfunction "1_1") (pintype "passive"))
      (node (ref "C310") (pin "1") (pinfunction "1_1") (pintype "passive"))
      (node (ref "C311") (pin "1") (pinfunction "1_1") (pintype "passive"))
      (node (ref "C312") (pin "1") (pinfunction "1_1") (pintype "passive"))
      (node (ref "C313") (pin "1") (pinfunction "1_1") (pintype "passive"))
      (node (ref "C314") (pin "1") (pinfunction "1_1") (pintype "passive"))
      (node (ref "C315") (pin "1") (pinfunction "1_1") (pintype "passive"))
      (node (ref "C316") (pin "1") (pinfunction "1_1") (pintype "passive"))
      (node (ref "C317") (pin "1") (pinfunction "1_1") (pintype "passive"))
      (node (ref "C318") (pin "1") (pinfunction "1_1") (pintype "passive"))
      (node (ref "C319") (pin "1") (pinfunction "1_1") (pintype "passive"))
      (node (ref "C320") (pin "1") (pinfunction "1_1") (pintype "passive"))
      (node (ref "C321") (pin "1") (pinfunction "1_1") (pintype "passive"))
      (node (ref "C322") (pin "1") (pinfunction "1_1") (pintype "passive"))
      (node (ref "U11") (pin "37") (pinfunction "AVDD33_37") (pintype "passive"))
      (node (ref "U11") (pin "40") (pinfunction "AVDD33_40") (pintype "passive"))
      (node (ref "U11") (pin "45") (pinfunction "AVDD33_45") (pintype "passive"))
      (node (ref "U11") (pin "48") (pinfunction "AVDD33_48") (pintype "passive"))
    )
    (net (code "5") (name "+5V0A") (class "Default")
      (node (ref "C304") (pin "1") (pinfunction "1_1") (pintype "passive"))
      (node (ref "C305") (pin "1") (pinfunction "1_1") (pintype "passive"))
      (node (ref "C306") (pin "1") (pinfunction "1_1") (pintype "passive"))
      (node (ref "C307") (pin "1") (pinfunction "1_1") (pintype "passive"))
      (node (ref "U12") (pin "8") (pinfunction "+VS_8") (pintype "passive"))
    )
    (net (code "6") (name "-5V0A") (class "Default")
      (node (ref "C335") (pin "1") (pinfunction "1_1") (pintype "passive"))
      (node (ref "C336") (pin "1") (pinfunction "1_1") (pintype "passive"))
      (node (ref "C337") (pin "1") (pinfunction "1_1") (pintype "passive"))
      (node (ref "C338") (pin "1") (pinfunction "1_1") (pintype "passive"))
      (node (ref "U12") (pin "4") (pinfunction "-VS_4") (pintype "passive"))
    )
    (net (code "7") (name "/CS") (class "Default")
      (node (ref "TP65") (pin "1") (pinfunction "A_1") (pintype "passive"))
      (node (ref "U11") (pin "33") (pinfunction "~{CS}_33") (pintype "passive"))
    )
    (net (code "8") (name "/D0_N") (class "Default")
      (node (ref "R151") (pin "1") (pinfunction "1_1") (pintype "passive"))
      (node (ref "U11") (pin "28") (pinfunction "D0N_28") (pintype "passive"))
    )
    (net (code "9") (name "/D0_P") (class "Default")
      (node (ref "R148") (pin "1") (pinfunction "1_1") (pintype "passive"))
      (node (ref "U11") (pin "27") (pinfunction "D0P_27") (pintype "passive"))
    )
    (net (code "10") (name "/D1_N") (class "Default")
      (node (ref "R144") (pin "1") (pinfunction "1_1") (pintype "passive"))
      (node (ref "U11") (pin "26") (pinfunction "D1N_26") (pintype "passive"))
    )
    (net (code "11") (name "/D1_P") (class "Default")
      (node (ref "R141") (pin "1") (pinfunction "1_1") (pintype "passive"))
      (node (ref "U11") (pin "25") (pinfunction "D1P_25") (pintype "passive"))
    )
    (net (code "12") (name "/D2_N") (class "Default")
      (node (ref "R138") (pin "1") (pinfunction "1_1") (pintype "passive"))
      (node (ref "U11") (pin "24") (pinfunction "D2N_24") (pintype "passive"))
    )
    (net (code "13") (name "/D2_P") (class "Default")
      (node (ref "R135") (pin "1") (pinfunction "1_1") (pintype "passive"))
      (node (ref "U11") (pin "23") (pinfunction "D2P_23") (pintype "passive"))
    )
    (net (code "14") (name "/D3_N") (class "Default")
      (node (ref "R150") (pin "1") (pinfunction "1_1") (pintype "passive"))
      (node (ref "U11") (pin "22") (pinfunction "D3N_22") (pintype "passive"))
    )
    (net (code "15") (name "/D3_P") (class "Default")
      (node (ref "R147") (pin "1") (pinfunction "1_1") (pintype "passive"))
      (node (ref "U11") (pin "21") (pinfunction "D3P_21") (pintype "passive"))
    )
    (net (code "16") (name "/D4_N") (class "Default")
      (node (ref "R143") (pin "1") (pinfunction "1_1") (pintype "passive"))
      (node (ref "U11") (pin "16") (pinfunction "D4N_16") (pintype "passive"))
    )
    (net (code "17") (name "/D4_P") (class "Default")
      (node (ref "R140") (pin "1") (pinfunction "1_1") (pintype "passive"))
      (node (ref "U11") (pin "15") (pinfunction "D4P_15") (pintype "passive"))
    )
    (net (code "18") (name "/D5_N") (class "Default")
      (node (ref "R137") (pin "1") (pinfunction "1_1") (pintype "passive"))
      (node (ref "U11") (pin "14") (pinfunction "D5N_14") (pintype "passive"))
    )
    (net (code "19") (name "/D5_P") (class "Default")
      (node (ref "R134") (pin "1") (pinfunction "1_1") (pintype "passive"))
      (node (ref "U11") (pin "13") (pinfunction "D5P_13") (pintype "passive"))
    )
    (net (code "20") (name "/D6_N") (class "Default")
      (node (ref "R149") (pin "1") (pinfunction "1_1") (pintype "passive"))
      (node (ref "U11") (pin "12") (pinfunction "D6N_12") (pintype "passive"))
    )
    (net (code "21") (name "/D6_P") (class "Default")
      (node (ref "R146") (pin "1") (pinfunction "1_1") (pintype "passive"))
      (node (ref "U11") (pin "11") (pinfunction "D6P_11") (pintype "passive"))
    )
    (net (code "22") (name "/D7_N") (class "Default")
      (node (ref "R142") (pin "1") (pinfunction "1_1") (pintype "passive"))
      (node (ref "U11") (pin "10") (pinfunction "D7N_10") (pintype "passive"))
    )
    (net (code "23") (name "/D7_P") (class "Default")
      (node (ref "R139") (pin "1") (pinfunction "1_1") (pintype "passive"))
      (node (ref "U11") (pin "9") (pinfunction "D7P_9") (pintype "passive"))
    )
    (net (code "24") (name "/DAC_CLK_N") (class "Default")
      (node (ref "R128") (pin "1") (pinfunction "1_1") (pintype "passive"))
      (node (ref "U11") (pin "4") (pinfunction "DACCLKN_4") (pintype "passive"))
    )
    (net (code "25") (name "/DAC_CLK_P") (class "Default")
      (node (ref "R129") (pin "1") (pinfunction "1_1") (pintype "passive"))
      (node (ref "U11") (pin "3") (pinfunction "DACCLKP_3") (pintype "passive"))
    )
    (net (code "26") (name "/DAC_SCLK") (class "Default")
      (node (ref "TP62") (pin "1") (pinfunction "A_1") (pintype "passive"))
      (node (ref "U11") (pin "32") (pinfunction "SCLK_32") (pintype "passive"))
    )
    (net (code "27") (name "/DCI_N") (class "Default")
      (node (ref "R136") (pin "1") (pinfunction "1_1") (pintype "passive"))
      (node (ref "U11") (pin "18") (pinfunction "DCIN_18") (pintype "passive"))
    )
    (net (code "28") (name "/DCI_P") (class "Default")
      (node (ref "R133") (pin "1") (pinfunction "1_1") (pintype "passive"))
      (node (ref "U11") (pin "17") (pinfunction "DCIP_17") (pintype "passive"))
    )
    (net (code "29") (name "/FRAME_N") (class "Default")
      (node (ref "R131") (pin "1") (pinfunction "1_1") (pintype "passive"))
      (node (ref "U11") (pin "20") (pinfunction "FRAMEN_20") (pintype "passive"))
    )
    (net (code "30") (name "/FRAME_P") (class "Default")
      (node (ref "R130") (pin "1") (pinfunction "1_1") (pintype "passive"))
      (node (ref "U11") (pin "19") (pinfunction "FRAMEP_19") (pintype "passive"))
    )
    (net (code "31") (name "/IRQ") (class "Default")
      (node (ref "U11") (pin "34") (pinfunction "~{IRQ}_34") (pintype "passive"))
    )
    (net (code "32") (name "/REF_CLK_N") (class "Default")
      (node (ref "TP67") (pin "1") (pinfunction "A_1") (pintype "passive"))
      (node (ref "U11") (pin "7") (pinfunction "REFCLKN_7") (pintype "passive"))
    )
    (net (code "33") (name "/REF_CLK_P") (class "Default")
      (node (ref "TP66") (pin "1") (pinfunction "A_1") (pintype "passive"))
      (node (ref "U11") (pin "6") (pinfunction "REFCLKP_6") (pintype "passive"))
    )
    (net (code "34") (name "/RST_DAC") (class "Default")
      (node (ref "R132") (pin "2") (pinfunction "2_2") (pintype "passive"))
      (node (ref "TP64") (pin "1") (pinfunction "A_1") (pintype "passive"))
      (node (ref "U11") (pin "36") (pinfunction "~{RESET}_36") (pintype "passive"))
    )
    (net (code "35") (name "/SDIO") (class "Default")
      (node (ref "TP63") (pin "1") (pinfunction "A_1") (pintype "passive"))
      (node (ref "U11") (pin "31") (pinfunction "SDIO_31") (pintype "passive"))
    )
    (net (code "36") (name "/SMA_OUT1") (class "Default")
      (node (ref "D8") (pin "1") (pinfunction "i/o_1") (pintype "passive"))
      (node (ref "J9") (pin "1") (pinfunction "1_1") (pintype "passive"))
      (node (ref "R116") (pin "2") (pinfunction "2_2") (pintype "passive"))
      (node (ref "TP57") (pin "1") (pinfunction "A_1") (pintype "passive"))
    )
    (net (code "37") (name "/SMA_OUT2") (class "Default")
      (node (ref "D9") (pin "1") (pinfunction "i/o_1") (pintype "passive"))
      (node (ref "J10") (pin "1") (pinfunction "1_1") (pintype "passive"))
      (node (ref "R123") (pin "2") (pinfunction "2_2") (pintype "passive"))
      (node (ref "TP61") (pin "1") (pinfunction "A_1") (pintype "passive"))
    )
    (net (code "38") (name "/TXENABLE") (class "Default")
      (node (ref "U11") (pin "30") (pinfunction "TXENABLE_30") (pintype "passive"))
    )
    (net (code "41") (name "GND") (class "Default")
      (node (ref "C293") (pin "2") (pinfunction "2_2") (pintype "passive"))
      (node (ref "C294") (pin "2") (pinfunction "2_2") (pintype "passive"))
      (node (ref "C295") (pin "2") (pinfunction "2_2") (pintype "passive"))
      (node (ref "C296") (pin "2") (pinfunction "2_2") (pintype "passive"))
      (node (ref "C297") (pin "2") (pinfunction "2_2") (pintype "passive"))
      (node (ref "C298") (pin "2") (pinfunction "2_2") (pintype "passive"))
      (node (ref "C299") (pin "2") (pinfunction "2_2") (pintype "passive"))
      (node (ref "C300") (pin "2") (pinfunction "2_2") (pintype "passive"))
      (node (ref "C301") (pin "2") (pinfunction "2_2") (pintype "passive"))
      (node (ref "C302") (pin "2") (pinfunction "2_2") (pintype "passive"))
      (node (ref "C303") (pin "2") (pinfunction "2_2") (pintype "passive"))
      (node (ref "C304") (pin "2") (pinfunction "2_2") (pintype "passive"))
      (node (ref "C305") (pin "2") (pinfunction "2_2") (pintype "passive"))
      (node (ref "C306") (pin "2") (pinfunction "2_2") (pintype "passive"))
      (node (ref "C307") (pin "2") (pinfunction "2_2") (pintype "passive"))
      (node (ref "C308") (pin "2") (pinfunction "2_2") (pintype "passive"))
      (node (ref "C309") (pin "2") (pinfunction "2_2") (pintype "passive"))
      (node (ref "C310") (pin "2") (pinfunction "2_2") (pintype "passive"))
      (node (ref "C311") (pin "2") (pinfunction "2_2") (pintype "passive"))
      (node (ref "C312") (pin "2") (pinfunction "2_2") (pintype "passive"))
      (node (ref "C313") (pin "2") (pinfunction "2_2") (pintype "passive"))
      (node (ref "C314") (pin "2") (pinfunction "2_2") (pintype "passive"))
      (node (ref "C315") (pin "2") (pinfunction "2_2") (pintype "passive"))
      (node (ref "C316") (pin "2") (pinfunction "2_2") (pintype "passive"))
      (node (ref "C317") (pin "2") (pinfunction "2_2") (pintype "passive"))
      (node (ref "C318") (pin "2") (pinfunction "2_2") (pintype "passive"))
      (node (ref "C319") (pin "2") (pinfunction "2_2") (pintype "passive"))
      (node (ref "C320") (pin "2") (pinfunction "2_2") (pintype "passive"))
      (node (ref "C321") (pin "2") (pinfunction "2_2") (pintype "passive"))
      (node (ref "C322") (pin "2") (pinfunction "2_2") (pintype "passive"))
      (node (ref "C323") (pin "2") (pinfunction "2_2") (pintype "passive"))
      (node (ref "C324") (pin "2") (pinfunction "2_2") (pintype "passive"))
      (node (ref "C325") (pin "2") (pinfunction "2_2") (pintype "passive"))
      (node (ref "C326") (pin "2") (pinfunction "2_2") (pintype "passive"))
      (node (ref "C327") (pin "2") (pinfunction "2_2") (pintype "passive"))
      (node (ref "C328") (pin "2") (pinfunction "2_2") (pintype "passive"))
      (node (ref "C329") (pin "2") (pinfunction "2_2") (pintype "passive"))
      (node (ref "C330") (pin "2") (pinfunction "2_2") (pintype "passive"))
      (node (ref "C331") (pin "2") (pinfunction "2_2") (pintype "passive"))
      (node (ref "C332") (pin "2") (pinfunction "2_2") (pintype "passive"))
      (node (ref "C333") (pin "2") (pinfunction "2_2") (pintype "passive"))
      (node (ref "C334") (pin "2") (pinfunction "2_2") (pintype "passive"))
      (node (ref "C335") (pin "2") (pinfunction "2_2") (pintype "passive"))
      (node (ref "C336") (pin "2") (pinfunction "2_2") (pintype "passive"))
      (node (ref "C337") (pin "2") (pinfunction "2_2") (pintype "passive"))
      (node (ref "C338") (pin "2") (pinfunction "2_2") (pintype "passive"))
      (node (ref "D8") (pin "2") (pinfunction "i/o_2") (pintype "passive"))
      (node (ref "D9") (pin "2") (pinfunction "i/o_2") (pintype "passive"))
      (node (ref "J10") (pin "2") (pinfunction "2_2") (pintype "passive"))
      (node (ref "J10") (pin "3") (pinfunction "3_3") (pintype "passive"))
      (node (ref "J10") (pin "4") (pinfunction "4_4") (pintype "passive"))
      (node (ref "J10") (pin "5") (pinfunction "5_5") (pintype "passive"))
      (node (ref "J9") (pin "2") (pinfunction "2_2") (pintype "passive"))
      (node (ref "J9") (pin "3") (pinfunction "3_3") (pintype "passive"))
      (node (ref "J9") (pin "4") (pinfunction "4_4") (pintype "passive"))
      (node (ref "J9") (pin "5") (pinfunction "5_5") (pintype "passive"))
      (node (ref "R118") (pin "2") (pinfunction "2_2") (pintype "passive"))
      (node (ref "R119") (pin "2") (pinfunction "2_2") (pintype "passive"))
      (node (ref "R120") (pin "2") (pinfunction "2_2") (pintype "passive"))
      (node (ref "R125") (pin "2") (pinfunction "2_2") (pintype "passive"))
      (node (ref "R126") (pin "2") (pinfunction "2_2") (pintype "passive"))
      (node (ref "R127") (pin "2") (pinfunction "2_2") (pintype "passive"))
      (node (ref "R128") (pin "2") (pinfunction "2_2") (pintype "passive"))
      (node (ref "R129") (pin "2") (pinfunction "2_2") (pintype "passive"))
      (node (ref "R145") (pin "2") (pinfunction "2_2") (pintype "passive"))
      (node (ref "TP58") (pin "1") (pinfunction "A_1") (pintype "passive"))
      (node (ref "U11") (pin "41") (pinfunction "AVSS_41") (pintype "passive"))
      (node (ref "U11") (pin "44") (pinfunction "AVSS_44") (pintype "passive"))
      (node (ref "U11") (pin "5") (pinfunction "CVSS_5") (pintype "passive"))
      (node (ref "U11") (pin "PAD") (pinfunction "AVSS_PAD") (pintype "passive"))
    )
    (net (code "42") (name "Net-(C291-Pad1)") (class "Default")
      (node (ref "C291") (pin "1") (pinfunction "1_1") (pintype "passive"))
      (node (ref "L9") (pin "2") (pinfunction "2_2") (pintype "passive"))
      (node (ref "R115") (pin "1") (pinfunction "1_1") (pintype "passive"))
    )
    (net (code "43") (name "Net-(C291-Pad2)") (class "Default")
      (node (ref "C291") (pin "2") (pinfunction "2_2") (pintype "passive"))
      (node (ref "L10") (pin "2") (pinfunction "2_2") (pintype "passive"))
      (node (ref "R117") (pin "1") (pinfunction "1_1") (pintype "passive"))
    )
    (net (code "44") (name "Net-(C292-Pad1)") (class "Default")
      (node (ref "C292") (pin "1") (pinfunction "1_1") (pintype "passive"))
      (node (ref "L11") (pin "2") (pinfunction "2_2") (pintype "passive"))
      (node (ref "R122") (pin "1") (pinfunction "1_1") (pintype "passive"))
    )
    (net (code "45") (name "Net-(C292-Pad2)") (class "Default")
      (node (ref "C292") (pin "2") (pinfunction "2_2") (pintype "passive"))
      (node (ref "L12") (pin "2") (pinfunction "2_2") (pintype "passive"))
      (node (ref "R124") (pin "1") (pinfunction "1_1") (pintype "passive"))
    )
    (net (code "46") (name "Net-(C293-Pad1)") (class "Default")
      (node (ref "C293") (pin "1") (pinfunction "1_1") (pintype "passive"))
      (node (ref "R130") (pin "2") (pinfunction "2_2") (pintype "passive"))
      (node (ref "R131") (pin "2") (pinfunction "2_2") (pintype "passive"))
    )
    (net (code "47") (name "Net-(C294-Pad1)") (class "Default")
      (node (ref "C294") (pin "1") (pinfunction "1_1") (pintype "passive"))
      (node (ref "R133") (pin "2") (pinfunction "2_2") (pintype "passive"))
      (node (ref "R136") (pin "2") (pinfunction "2_2") (pintype "passive"))
    )
    (net (code "48") (name "Net-(C295-Pad1)") (class "Default")
      (node (ref "C295") (pin "1") (pinfunction "1_1") (pintype "passive"))
      (node (ref "R134") (pin "2") (pinfunction "2_2") (pintype "passive"))
      (node (ref "R137") (pin "2") (pinfunction "2_2") (pintype "passive"))
    )
    (net (code "49") (name "Net-(C296-Pad1)") (class "Default")
      (node (ref "C296") (pin "1") (pinfunction "1_1") (pintype "passive"))
      (node (ref "R135") (pin "2") (pinfunction "2_2") (pintype "passive"))
      (node (ref "R138") (pin "2") (pinfunction "2_2") (pintype "passive"))
    )
    (net (code "50") (name "Net-(C297-Pad1)") (class "Default")
      (node (ref "C297") (pin "1") (pinfunction "1_1") (pintype "passive"))
      (node (ref "R139") (pin "2") (pinfunction "2_2") (pintype "passive"))
      (node (ref "R142") (pin "2") (pinfunction "2_2") (pintype "passive"))
    )
    (net (code "51") (name "Net-(C298-Pad1)") (class "Default")
      (node (ref "C298") (pin "1") (pinfunction "1_1") (pintype "passive"))
      (node (ref "R140") (pin "2") (pinfunction "2_2") (pintype "passive"))
      (node (ref "R143") (pin "2") (pinfunction "2_2") (pintype "passive"))
    )
    (net (code "52") (name "Net-(C299-Pad1)") (class "Default")
      (node (ref "C299") (pin "1") (pinfunction "1_1") (pintype "passive"))
      (node (ref "R141") (pin "2") (pinfunction "2_2") (pintype "passive"))
      (node (ref "R144") (pin "2") (pinfunction "2_2") (pintype "passive"))
    )
    (net (code "53") (name "Net-(C301-Pad1)") (class "Default")
      (node (ref "C301") (pin "1") (pinfunction "1_1") (pintype "passive"))
      (node (ref "R146") (pin "2") (pinfunction "2_2") (pintype "passive"))
      (node (ref "R149") (pin "2") (pinfunction "2_2") (pintype "passive"))
    )
    (net (code "54") (name "Net-(C302-Pad1)") (class "Default")
      (node (ref "C302") (pin "1") (pinfunction "1_1") (pintype "passive"))
      (node (ref "R147") (pin "2") (pinfunction "2_2") (pintype "passive"))
      (node (ref "R150") (pin "2") (pinfunction "2_2") (pintype "passive"))
    )
    (net (code "55") (name "Net-(C303-Pad1)") (class "Default")
      (node (ref "C303") (pin "1") (pinfunction "1_1") (pintype "passive"))
      (node (ref "R148") (pin "2") (pinfunction "2_2") (pintype "passive"))
      (node (ref "R151") (pin "2") (pinfunction "2_2") (pintype "passive"))
    )
    (net (code "56") (name "Net-(TP55-A)") (class "Default")
      (node (ref "L10") (pin "1") (pinfunction "1_1") (pintype "passive"))
      (node (ref "R118") (pin "1") (pinfunction "1_1") (pintype "passive"))
      (node (ref "TP55") (pin "1") (pinfunction "A_1") (pintype "passive"))
      (node (ref "U11") (pin "46") (pinfunction "IOUT1N_46") (pintype "passive"))
    )
    (net (code "57") (name "Net-(TP56-A)") (class "Default")
      (node (ref "L9") (pin "1") (pinfunction "1_1") (pintype "passive"))
      (node (ref "R119") (pin "1") (pinfunction "1_1") (pintype "passive"))
      (node (ref "TP56") (pin "1") (pinfunction "A_1") (pintype "passive"))
      (node (ref "U11") (pin "47") (pinfunction "IOUT1P_47") (pintype "passive"))
    )
    (net (code "58") (name "Net-(TP59-A)") (class "Default")
      (node (ref "L12") (pin "1") (pinfunction "1_1") (pintype "passive"))
      (node (ref "R125") (pin "1") (pinfunction "1_1") (pintype "passive"))
      (node (ref "TP59") (pin "1") (pinfunction "A_1") (pintype "passive"))
      (node (ref "U11") (pin "39") (pinfunction "IOUT2N_39") (pintype "passive"))
    )
    (net (code "59") (name "Net-(TP60-A)") (class "Default")
      (node (ref "L11") (pin "1") (pinfunction "1_1") (pintype "passive"))
      (node (ref "R126") (pin "1") (pinfunction "1_1") (pintype "passive"))
      (node (ref "TP60") (pin "1") (pinfunction "A_1") (pintype "passive"))
      (node (ref "U11") (pin "38") (pinfunction "IOUT2P_38") (pintype "passive"))
    )
    (net (code "60") (name "Net-(U11B-FSADJ)") (class "Default")
      (node (ref "R145") (pin "1") (pinfunction "1_1") (pintype "passive"))
      (node (ref "U11") (pin "43") (pinfunction "FSADJ_43") (pintype "passive"))
    )
    (net (code "61") (name "Net-(U11B-REFIO)") (class "Default")
      (node (ref "C300") (pin "1") (pinfunction "1_1") (pintype "passive"))
      (node (ref "U11") (pin "42") (pinfunction "REFIO_42") (pintype "passive"))
    )
    (net (code "62") (name "Net-(U12A-+IN1)") (class "Default")
      (node (ref "R117") (pin "2") (pinfunction "2_2") (pintype "passive"))
      (node (ref "R120") (pin "1") (pinfunction "1_1") (pintype "passive"))
      (node (ref "U12") (pin "3") (pinfunction "+IN1_3") (pintype "passive"))
    )
    (net (code "63") (name "Net-(U12A--IN1)") (class "Default")
      (node (ref "R114") (pin "2") (pinfunction "2_2") (pintype "passive"))
      (node (ref "R115") (pin "2") (pinfunction "2_2") (pintype "passive"))
      (node (ref "U12") (pin "2") (pinfunction "-IN1_2") (pintype "passive"))
    )
    (net (code "64") (name "Net-(U12A-OUT1)") (class "Default")
      (node (ref "R114") (pin "1") (pinfunction "1_1") (pintype "passive"))
      (node (ref "R116") (pin "1") (pinfunction "1_1") (pintype "passive"))
      (node (ref "U12") (pin "1") (pinfunction "OUT1_1") (pintype "passive"))
    )
    (net (code "65") (name "Net-(U12B-+IN2)") (class "Default")
      (node (ref "R124") (pin "2") (pinfunction "2_2") (pintype "passive"))
      (node (ref "R127") (pin "1") (pinfunction "1_1") (pintype "passive"))
      (node (ref "U12") (pin "5") (pinfunction "+IN2_5") (pintype "passive"))
    )
    (net (code "66") (name "Net-(U12B--IN2)") (class "Default")
      (node (ref "R121") (pin "2") (pinfunction "2_2") (pintype "passive"))
      (node (ref "R122") (pin "2") (pinfunction "2_2") (pintype "passive"))
      (node (ref "U12") (pin "6") (pinfunction "-IN2_6") (pintype "passive"))
    )
    (net (code "67") (name "Net-(U12B-OUT2)") (class "Default")
      (node (ref "R121") (pin "1") (pinfunction "1_1") (pintype "passive"))
      (node (ref "R123") (pin "1") (pinfunction "1_1") (pintype "passive"))
      (node (ref "U12") (pin "7") (pinfunction "OUT2_7") (pintype "passive"))
    )
  )
)
